# LCD.net
KiCad netlist of a schematic drawn in Altium Designer
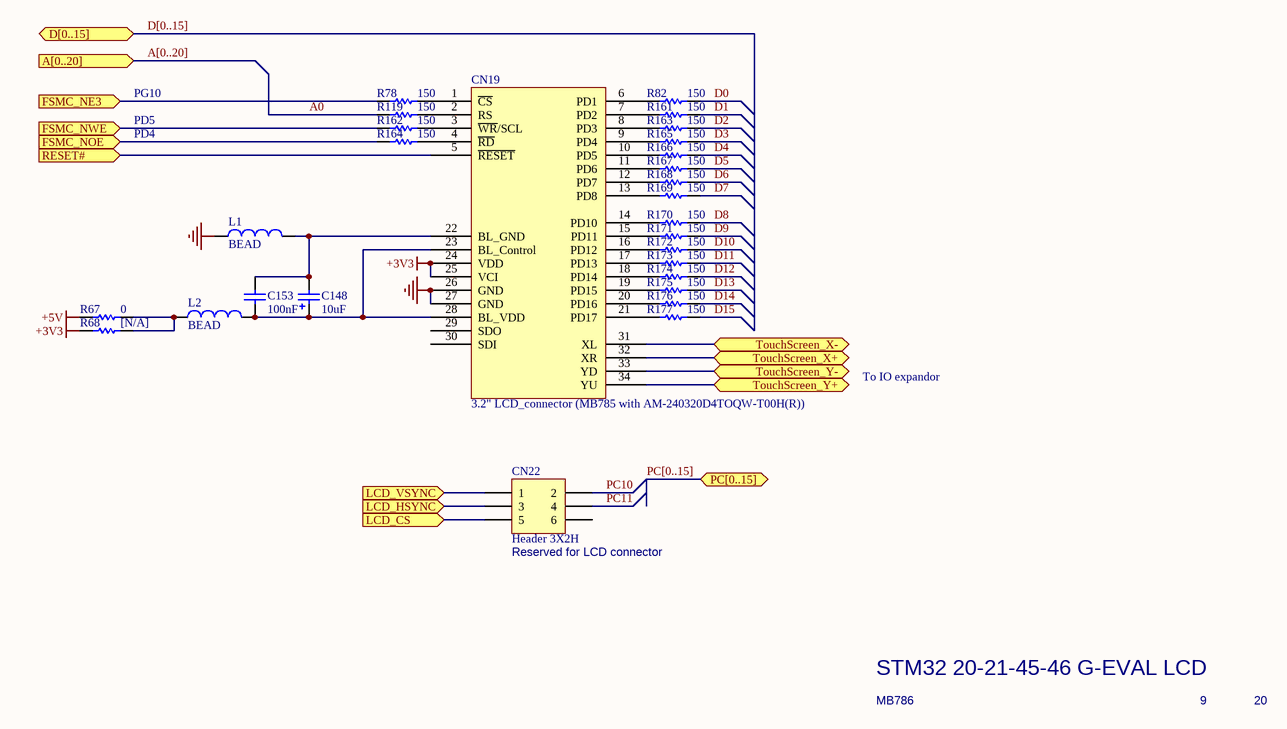
[diagram p0: LCD.SchDoc]

(export (version "E")
  (design (tool "Eeschema 10.0.6"))
  (components
    (comp (ref "C148")
      (value "10uF")
      (footprint "TAN-A")
      (description "Polarized Capacitor (Radial)")
      (fields (field (name "PUBLISHER") "Altium Limited"))
      (libsource (lib "Miscellaneous Devices") (part "Cap Pol1"))
    )
    (comp (ref "C153")
      (value "100nF")
      (footprint "0402C")
      (description "Capacitor")
      (fields (field (name "PUBLISHER") "Altium Limited"))
      (libsource (lib "Miscellaneous Devices") (part "Cap"))
    )
    (comp (ref "CN19")
      (value "3.2\" LCD_connector (MB785 with AM-240320D4TOQW-T00H(R))")
      (footprint "AM240*320AA")
      (libsource (lib "3.2LCD_daughterboard") (part "3.2LCD_connector"))
    )
    (comp (ref "CN22")
      (value "Header 3X2H")
      (footprint "HDR2X3H")
      (description "Header, 3-Pin, Dual row, Right Angle")
      (fields (field (name "PUBLISHER") "Altium Limited"))
      (libsource (lib "Miscellaneous Connectors") (part "Header 3X2H"))
    )
    (comp (ref "L1")
      (value "BEAD")
      (footprint "0603L")
      (description "Inductor")
      (fields (field (name "PUBLISHER") "Altium Limited"))
      (libsource (lib "Miscellaneous Devices") (part "Inductor"))
    )
    (comp (ref "L2")
      (value "BEAD")
      (footprint "0603L")
      (description "Inductor")
      (fields (field (name "PUBLISHER") "Altium Limited"))
      (libsource (lib "Miscellaneous Devices") (part "Inductor"))
    )
    (comp (ref "R67")
      (value "0")
      (footprint "0603R")
      (description "Resistor")
      (fields (field (name "PUBLISHER") "Altium Limited"))
      (libsource (lib "Miscellaneous Devices") (part "Res1"))
    )
    (comp (ref "R68")
      (value "[N/A]")
      (footprint "0603R")
      (description "Resistor")
      (fields (field (name "PUBLISHER") "Altium Limited"))
      (libsource (lib "Miscellaneous Devices") (part "Res1"))
    )
    (comp (ref "R78")
      (value "150")
      (footprint "0603R")
      (description "Resistor")
      (fields (field (name "PUBLISHER") "Altium Limited"))
      (libsource (lib "Miscellaneous Devices") (part "Res1"))
    )
    (comp (ref "R82")
      (value "150")
      (footprint "0603R")
      (description "Resistor")
      (fields (field (name "PUBLISHER") "Altium Limited"))
      (libsource (lib "Miscellaneous Devices") (part "Res1"))
    )
    (comp (ref "R119")
      (value "150")
      (footprint "0603R")
      (description "Resistor")
      (fields (field (name "PUBLISHER") "Altium Limited"))
      (libsource (lib "Miscellaneous Devices") (part "Res1"))
    )
    (comp (ref "R161")
      (value "150")
      (footprint "0603R")
      (description "Resistor")
      (fields (field (name "PUBLISHER") "Altium Limited"))
      (libsource (lib "Miscellaneous Devices") (part "Res1"))
    )
    (comp (ref "R162")
      (value "150")
      (footprint "0603R")
      (description "Resistor")
      (fields (field (name "PUBLISHER") "Altium Limited"))
      (libsource (lib "Miscellaneous Devices") (part "Res1"))
    )
    (comp (ref "R163")
      (value "150")
      (footprint "0603R")
      (description "Resistor")
      (fields (field (name "PUBLISHER") "Altium Limited"))
      (libsource (lib "Miscellaneous Devices") (part "Res1"))
    )
    (comp (ref "R164")
      (value "150")
      (footprint "0603R")
      (description "Resistor")
      (fields (field (name "PUBLISHER") "Altium Limited"))
      (libsource (lib "Miscellaneous Devices") (part "Res1"))
    )
    (comp (ref "R165")
      (value "150")
      (footprint "0603R")
      (description "Resistor")
      (fields (field (name "PUBLISHER") "Altium Limited"))
      (libsource (lib "Miscellaneous Devices") (part "Res1"))
    )
    (comp (ref "R166")
      (value "150")
      (footprint "0603R")
      (description "Resistor")
      (fields (field (name "PUBLISHER") "Altium Limited"))
      (libsource (lib "Miscellaneous Devices") (part "Res1"))
    )
    (comp (ref "R167")
      (value "150")
      (footprint "0603R")
      (description "Resistor")
      (fields (field (name "PUBLISHER") "Altium Limited"))
      (libsource (lib "Miscellaneous Devices") (part "Res1"))
    )
    (comp (ref "R168")
      (value "150")
      (footprint "0603R")
      (description "Resistor")
      (fields (field (name "PUBLISHER") "Altium Limited"))
      (libsource (lib "Miscellaneous Devices") (part "Res1"))
    )
    (comp (ref "R169")
      (value "150")
      (footprint "0603R")
      (description "Resistor")
      (fields (field (name "PUBLISHER") "Altium Limited"))
      (libsource (lib "Miscellaneous Devices") (part "Res1"))
    )
    (comp (ref "R170")
      (value "150")
      (footprint "0603R")
      (description "Resistor")
      (fields (field (name "PUBLISHER") "Altium Limited"))
      (libsource (lib "Miscellaneous Devices") (part "Res1"))
    )
    (comp (ref "R171")
      (value "150")
      (footprint "0603R")
      (description "Resistor")
      (fields (field (name "PUBLISHER") "Altium Limited"))
      (libsource (lib "Miscellaneous Devices") (part "Res1"))
    )
    (comp (ref "R172")
      (value "150")
      (footprint "0603R")
      (description "Resistor")
      (fields (field (name "PUBLISHER") "Altium Limited"))
      (libsource (lib "Miscellaneous Devices") (part "Res1"))
    )
    (comp (ref "R173")
      (value "150")
      (footprint "0603R")
      (description "Resistor")
      (fields (field (name "PUBLISHER") "Altium Limited"))
      (libsource (lib "Miscellaneous Devices") (part "Res1"))
    )
    (comp (ref "R174")
      (value "150")
      (footprint "0603R")
      (description "Resistor")
      (fields (field (name "PUBLISHER") "Altium Limited"))
      (libsource (lib "Miscellaneous Devices") (part "Res1"))
    )
    (comp (ref "R175")
      (value "150")
      (footprint "0603R")
      (description "Resistor")
      (fields (field (name "PUBLISHER") "Altium Limited"))
      (libsource (lib "Miscellaneous Devices") (part "Res1"))
    )
    (comp (ref "R176")
      (value "150")
      (footprint "0603R")
      (description "Resistor")
      (fields (field (name "PUBLISHER") "Altium Limited"))
      (libsource (lib "Miscellaneous Devices") (part "Res1"))
    )
    (comp (ref "R177")
      (value "150")
      (footprint "0603R")
      (description "Resistor")
      (fields (field (name "PUBLISHER") "Altium Limited"))
      (libsource (lib "Miscellaneous Devices") (part "Res1"))
    )
  )
  (nets
    (net (code "35") (name "+3V3") (class "Default")
      (node (ref "CN19") (pin "24") (pinfunction "VDD_24") (pintype "passive"))
      (node (ref "CN19") (pin "25") (pinfunction "VCI_25") (pintype "passive"))
      (node (ref "R68") (pin "1") (pinfunction "1_1") (pintype "passive"))
    )
    (net (code "36") (name "+5V") (class "Default")
      (node (ref "R67") (pin "1") (pinfunction "1_1") (pintype "passive"))
    )
    (net (code "37") (name "/A0") (class "Default")
      (node (ref "R119") (pin "1") (pinfunction "1_1") (pintype "passive"))
    )
    (net (code "39") (name "/D0") (class "Default")
      (node (ref "R82") (pin "2") (pinfunction "2_2") (pintype "passive"))
    )
    (net (code "40") (name "/D1") (class "Default")
      (node (ref "R161") (pin "2") (pinfunction "2_2") (pintype "passive"))
    )
    (net (code "41") (name "/D2") (class "Default")
      (node (ref "R163") (pin "2") (pinfunction "2_2") (pintype "passive"))
    )
    (net (code "42") (name "/D3") (class "Default")
      (node (ref "R165") (pin "2") (pinfunction "2_2") (pintype "passive"))
    )
    (net (code "43") (name "/D4") (class "Default")
      (node (ref "R166") (pin "2") (pinfunction "2_2") (pintype "passive"))
    )
    (net (code "44") (name "/D5") (class "Default")
      (node (ref "R167") (pin "2") (pinfunction "2_2") (pintype "passive"))
    )
    (net (code "45") (name "/D6") (class "Default")
      (node (ref "R168") (pin "2") (pinfunction "2_2") (pintype "passive"))
    )
    (net (code "46") (name "/D7") (class "Default")
      (node (ref "R169") (pin "2") (pinfunction "2_2") (pintype "passive"))
    )
    (net (code "47") (name "/D8") (class "Default")
      (node (ref "R170") (pin "2") (pinfunction "2_2") (pintype "passive"))
    )
    (net (code "48") (name "/D9") (class "Default")
      (node (ref "R171") (pin "2") (pinfunction "2_2") (pintype "passive"))
    )
    (net (code "49") (name "/D10") (class "Default")
      (node (ref "R172") (pin "2") (pinfunction "2_2") (pintype "passive"))
    )
    (net (code "50") (name "/D11") (class "Default")
      (node (ref "R173") (pin "2") (pinfunction "2_2") (pintype "passive"))
    )
    (net (code "51") (name "/D12") (class "Default")
      (node (ref "R174") (pin "2") (pinfunction "2_2") (pintype "passive"))
    )
    (net (code "52") (name "/D13") (class "Default")
      (node (ref "R175") (pin "2") (pinfunction "2_2") (pintype "passive"))
    )
    (net (code "53") (name "/D14") (class "Default")
      (node (ref "R176") (pin "2") (pinfunction "2_2") (pintype "passive"))
    )
    (net (code "54") (name "/D15") (class "Default")
      (node (ref "R177") (pin "2") (pinfunction "2_2") (pintype "passive"))
    )
    (net (code "56") (name "/FSMC_NE3") (class "Default")
      (node (ref "R78") (pin "1") (pinfunction "1_1") (pintype "passive"))
    )
    (net (code "57") (name "/FSMC_NOE") (class "Default")
      (node (ref "R164") (pin "1") (pinfunction "1_1") (pintype "passive"))
    )
    (net (code "58") (name "/FSMC_NWE") (class "Default")
      (node (ref "R162") (pin "1") (pinfunction "1_1") (pintype "passive"))
    )
    (net (code "59") (name "/LCD_CS") (class "Default")
      (node (ref "CN22") (pin "5") (pinfunction "5_5") (pintype "passive"))
    )
    (net (code "60") (name "/LCD_HSYNC") (class "Default")
      (node (ref "CN22") (pin "3") (pinfunction "3_3") (pintype "passive"))
    )
    (net (code "61") (name "/LCD_VSYNC") (class "Default")
      (node (ref "CN22") (pin "1") (pinfunction "1_1") (pintype "passive"))
    )
    (net (code "62") (name "/PC10") (class "Default")
      (node (ref "CN22") (pin "2") (pinfunction "2_2") (pintype "passive"))
    )
    (net (code "63") (name "/PC11") (class "Default")
      (node (ref "CN22") (pin "4") (pinfunction "4_4") (pintype "passive"))
    )
    (net (code "65") (name "/RESET#") (class "Default")
      (node (ref "CN19") (pin "5") (pinfunction "~{RESET}_5") (pintype "passive"))
    )
    (net (code "66") (name "/TouchScreen_X+") (class "Default")
      (node (ref "CN19") (pin "32") (pinfunction "XR_32") (pintype "passive"))
    )
    (net (code "67") (name "/TouchScreen_X-") (class "Default")
      (node (ref "CN19") (pin "31") (pinfunction "XL_31") (pintype "passive"))
    )
    (net (code "68") (name "/TouchScreen_Y+") (class "Default")
      (node (ref "CN19") (pin "34") (pinfunction "YU_34") (pintype "passive"))
    )
    (net (code "69") (name "/TouchScreen_Y-") (class "Default")
      (node (ref "CN19") (pin "33") (pinfunction "YD_33") (pintype "passive"))
    )
    (net (code "70") (name "GND") (class "Default")
      (node (ref "CN19") (pin "26") (pinfunction "GND_26") (pintype "passive"))
      (node (ref "CN19") (pin "27") (pinfunction "GND_27") (pintype "passive"))
      (node (ref "L1") (pin "1") (pinfunction "1_1") (pintype "passive"))
    )
    (net (code "71") (name "Net-(CN19-BL_Control)") (class "Default")
      (node (ref "C148") (pin "1") (pinfunction "1_1") (pintype "passive"))
      (node (ref "C153") (pin "2") (pinfunction "2_2") (pintype "passive"))
      (node (ref "CN19") (pin "23") (pinfunction "BL_Control_23") (pintype "passive"))
      (node (ref "CN19") (pin "28") (pinfunction "BL_VDD_28") (pintype "passive"))
      (node (ref "L2") (pin "2") (pinfunction "2_2") (pintype "passive"))
    )
    (net (code "72") (name "Net-(CN19-BL_GND)") (class "Default")
      (node (ref "C148") (pin "2") (pinfunction "2_2") (pintype "passive"))
      (node (ref "C153") (pin "1") (pinfunction "1_1") (pintype "passive"))
      (node (ref "CN19") (pin "22") (pinfunction "BL_GND_22") (pintype "passive"))
      (node (ref "L1") (pin "2") (pinfunction "2_2") (pintype "passive"))
    )
    (net (code "73") (name "Net-(CN19-PD1)") (class "Default")
      (node (ref "CN19") (pin "6") (pinfunction "PD1_6") (pintype "passive"))
      (node (ref "R82") (pin "1") (pinfunction "1_1") (pintype "passive"))
    )
    (net (code "74") (name "Net-(CN19-PD2)") (class "Default")
      (node (ref "CN19") (pin "7") (pinfunction "PD2_7") (pintype "passive"))
      (node (ref "R161") (pin "1") (pinfunction "1_1") (pintype "passive"))
    )
    (net (code "75") (name "Net-(CN19-PD3)") (class "Default")
      (node (ref "CN19") (pin "8") (pinfunction "PD3_8") (pintype "passive"))
      (node (ref "R163") (pin "1") (pinfunction "1_1") (pintype "passive"))
    )
    (net (code "76") (name "Net-(CN19-PD4)") (class "Default")
      (node (ref "CN19") (pin "9") (pinfunction "PD4_9") (pintype "passive"))
      (node (ref "R165") (pin "1") (pinfunction "1_1") (pintype "passive"))
    )
    (net (code "77") (name "Net-(CN19-PD5)") (class "Default")
      (node (ref "CN19") (pin "10") (pinfunction "PD5_10") (pintype "passive"))
      (node (ref "R166") (pin "1") (pinfunction "1_1") (pintype "passive"))
    )
    (net (code "78") (name "Net-(CN19-PD6)") (class "Default")
      (node (ref "CN19") (pin "11") (pinfunction "PD6_11") (pintype "passive"))
      (node (ref "R167") (pin "1") (pinfunction "1_1") (pintype "passive"))
    )
    (net (code "79") (name "Net-(CN19-PD7)") (class "Default")
      (node (ref "CN19") (pin "12") (pinfunction "PD7_12") (pintype "passive"))
      (node (ref "R168") (pin "1") (pinfunction "1_1") (pintype "passive"))
    )
    (net (code "80") (name "Net-(CN19-PD8)") (class "Default")
      (node (ref "CN19") (pin "13") (pinfunction "PD8_13") (pintype "passive"))
      (node (ref "R169") (pin "1") (pinfunction "1_1") (pintype "passive"))
    )
    (net (code "81") (name "Net-(CN19-PD10)") (class "Default")
      (node (ref "CN19") (pin "14") (pinfunction "PD10_14") (pintype "passive"))
      (node (ref "R170") (pin "1") (pinfunction "1_1") (pintype "passive"))
    )
    (net (code "82") (name "Net-(CN19-PD11)") (class "Default")
      (node (ref "CN19") (pin "15") (pinfunction "PD11_15") (pintype "passive"))
      (node (ref "R171") (pin "1") (pinfunction "1_1") (pintype "passive"))
    )
    (net (code "83") (name "Net-(CN19-PD12)") (class "Default")
      (node (ref "CN19") (pin "16") (pinfunction "PD12_16") (pintype "passive"))
      (node (ref "R172") (pin "1") (pinfunction "1_1") (pintype "passive"))
    )
    (net (code "84") (name "Net-(CN19-PD13)") (class "Default")
      (node (ref "CN19") (pin "17") (pinfunction "PD13_17") (pintype "passive"))
      (node (ref "R173") (pin "1") (pinfunction "1_1") (pintype "passive"))
    )
    (net (code "85") (name "Net-(CN19-PD14)") (class "Default")
      (node (ref "CN19") (pin "18") (pinfunction "PD14_18") (pintype "passive"))
      (node (ref "R174") (pin "1") (pinfunction "1_1") (pintype "passive"))
    )
    (net (code "86") (name "Net-(CN19-PD15)") (class "Default")
      (node (ref "CN19") (pin "19") (pinfunction "PD15_19") (pintype "passive"))
      (node (ref "R175") (pin "1") (pinfunction "1_1") (pintype "passive"))
    )
    (net (code "87") (name "Net-(CN19-PD16)") (class "Default")
      (node (ref "CN19") (pin "20") (pinfunction "PD16_20") (pintype "passive"))
      (node (ref "R176") (pin "1") (pinfunction "1_1") (pintype "passive"))
    )
    (net (code "88") (name "Net-(CN19-PD17)") (class "Default")
      (node (ref "CN19") (pin "21") (pinfunction "PD17_21") (pintype "passive"))
      (node (ref "R177") (pin "1") (pinfunction "1_1") (pintype "passive"))
    )
    (net (code "89") (name "Net-(CN19-RS)") (class "Default")
      (node (ref "CN19") (pin "2") (pinfunction "RS_2") (pintype "passive"))
      (node (ref "R119") (pin "2") (pinfunction "2_2") (pintype "passive"))
    )
    (net (code "90") (name "Net-(CN19-~{CS})") (class "Default")
      (node (ref "CN19") (pin "1") (pinfunction "~{CS}_1") (pintype "passive"))
      (node (ref "R78") (pin "2") (pinfunction "2_2") (pintype "passive"))
    )
    (net (code "91") (name "Net-(CN19-~{RD})") (class "Default")
      (node (ref "CN19") (pin "4") (pinfunction "~{RD}_4") (pintype "passive"))
      (node (ref "R164") (pin "2") (pinfunction "2_2") (pintype "passive"))
    )
    (net (code "92") (name "Net-(CN19-~{WR}{slash}SCL)") (class "Default")
      (node (ref "CN19") (pin "3") (pinfunction "~{WR}/SCL_3") (pintype "passive"))
      (node (ref "R162") (pin "2") (pinfunction "2_2") (pintype "passive"))
    )
    (net (code "93") (name "Net-(L2-Pad1)") (class "Default")
      (node (ref "L2") (pin "1") (pinfunction "1_1") (pintype "passive"))
      (node (ref "R67") (pin "2") (pinfunction "2_2") (pintype "passive"))
      (node (ref "R68") (pin "2") (pinfunction "2_2") (pintype "passive"))
    )
    (net (code "94") (name "unconnected-(CN19-SDI-Pad30)") (class "Default")
      (node (ref "CN19") (pin "30") (pinfunction "SDI_30") (pintype "passive"))
    )
    (net (code "95") (name "unconnected-(CN19-SDO-Pad29)") (class "Default")
      (node (ref "CN19") (pin "29") (pinfunction "SDO_29") (pintype "passive"))
    )
    (net (code "96") (name "unconnected-(CN22-Pad6)") (class "Default")
      (node (ref "CN22") (pin "6") (pinfunction "6_6") (pintype "passive"))
    )
  )
)
